# EJECTION_CIRCUIT.net
KiCad netlist of a schematic drawn in Altium Designer
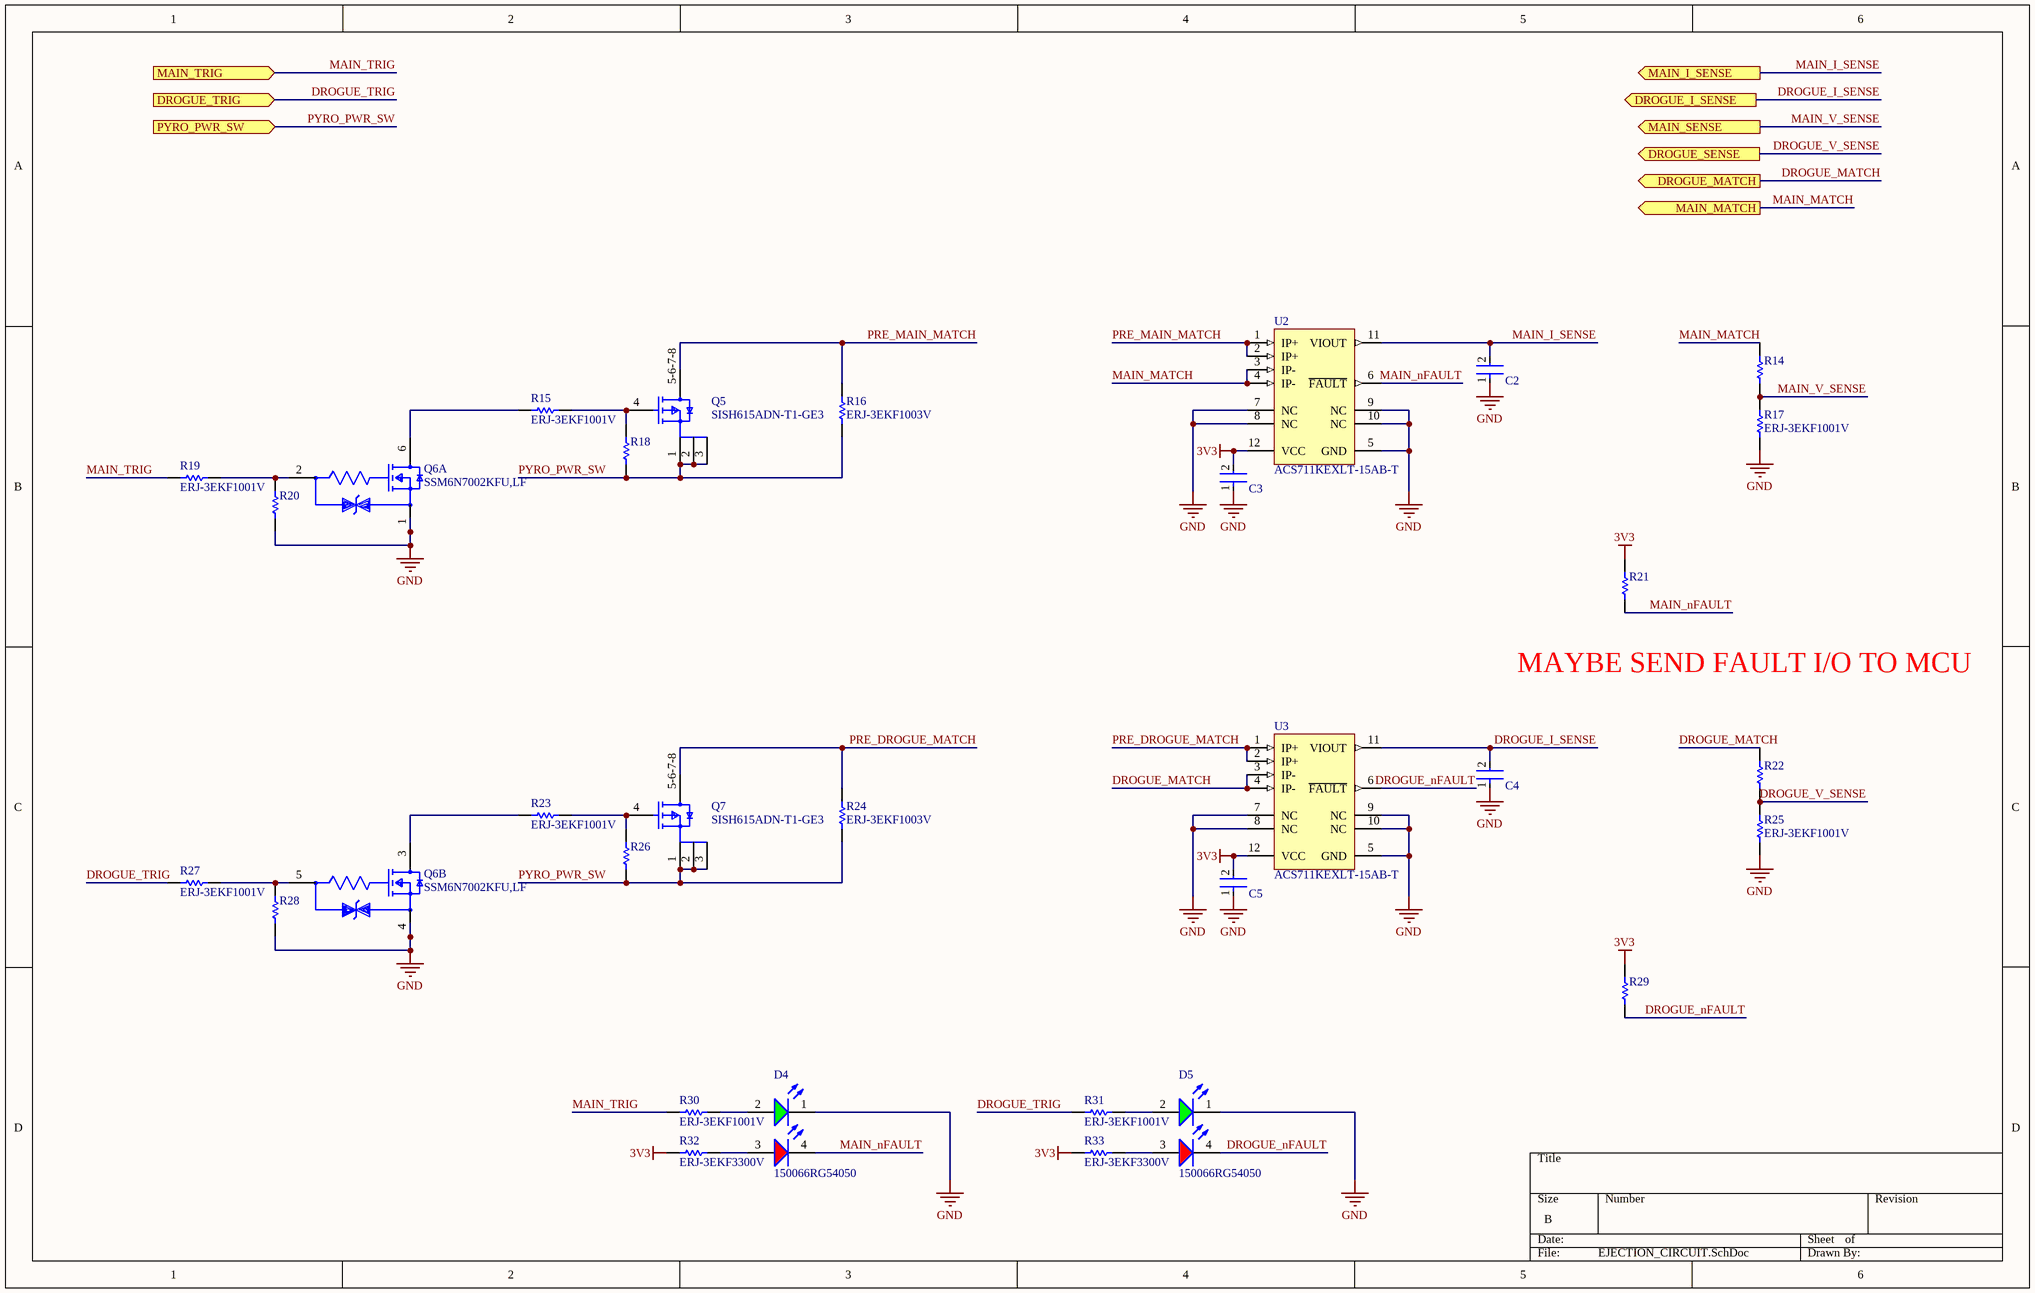
[diagram p0: EJECTION_CIRCUIT.SchDoc]

(export (version "E")
  (design (tool "Eeschema 10.0.6"))
  (components
    (comp (ref "C2")
      (value "C0402C104K8PACTU")
      (footprint "FP-C0402-BB-MFG")
      (description "CAP CER 0.1UF 10V X5R 0402")
      (fields (field (name "MANUFACTURER") "Kemet") (field (name "TOLERANCE") "0.1"))
      (libsource (lib "Altium Content Vault") (part "b4654b650e69147ec39a6b967a45e02"))
    )
    (comp (ref "C3")
      (value "C0402C104K8PACTU")
      (footprint "FP-C0402-BB-MFG")
      (description "CAP CER 0.1UF 10V X5R 0402")
      (fields (field (name "MANUFACTURER") "Kemet") (field (name "TOLERANCE") "0.1"))
      (libsource (lib "Altium Content Vault") (part "b4654b650e69147ec39a6b967a45e02"))
    )
    (comp (ref "C4")
      (value "C0402C104K8PACTU")
      (footprint "FP-C0402-BB-MFG")
      (description "CAP CER 0.1UF 10V X5R 0402")
      (fields (field (name "MANUFACTURER") "Kemet") (field (name "TOLERANCE") "0.1"))
      (libsource (lib "Altium Content Vault") (part "b4654b650e69147ec39a6b967a45e02"))
    )
    (comp (ref "C5")
      (value "C0402C104K8PACTU")
      (footprint "FP-C0402-BB-MFG")
      (description "CAP CER 0.1UF 10V X5R 0402")
      (fields (field (name "MANUFACTURER") "Kemet") (field (name "TOLERANCE") "0.1"))
      (libsource (lib "Altium Content Vault") (part "b4654b650e69147ec39a6b967a45e02"))
    )
    (comp (ref "D4")
      (value "150066RG54050")
      (footprint "WL-SBCD_0606")
      (description "Led, Red/Grn, 180Mcd/230Mcd, 624Nm/525Nm Rohs Compliant: Yes")
      (fields (field (name "SOURCE") "rgled.SchLib"))
      (libsource (lib "Space Concordia") (part "CMP-004-00034-2"))
    )
    (comp (ref "D5")
      (value "150066RG54050")
      (footprint "WL-SBCD_0606")
      (description "Led, Red/Grn, 180Mcd/230Mcd, 624Nm/525Nm Rohs Compliant: Yes")
      (fields (field (name "SOURCE") "rgled.SchLib"))
      (libsource (lib "Space Concordia") (part "CMP-004-00034-2"))
    )
    (comp (ref "Q5")
      (value "SISH615ADN-T1-GE3")
      (footprint "SISH615ADN-T1-GE3-Footprint-1")
      (description "Trans MOSFET P-CH 20V 22.1A 8-Pin PowerPAK 1212 EP T/R")
      (libsource (lib "Space Concordia") (part "CMP-013-00036-4"))
    )
    (comp (ref "Q6")
      (value "SSM6N7002KFU,LF")
      (footprint "FP-SSOP6-P-0_65A-MFG")
      (description "MOSFET 2N-CH 60V 0.3A")
      (libsource (lib "Altium Content Vault") (part "088aa6ac103fdeebe0d1c52ece6b7b9"))
    )
    (comp (ref "Q7")
      (value "SISH615ADN-T1-GE3")
      (footprint "SISH615ADN-T1-GE3-Footprint-1")
      (description "Trans MOSFET P-CH 20V 22.1A 8-Pin PowerPAK 1212 EP T/R")
      (libsource (lib "Space Concordia") (part "CMP-013-00036-4"))
    )
    (comp (ref "R14")
      (value "ERJ3EKF1002V")
      (footprint "RESC1609X55X30LL15T15")
      (description "Chip Resistor, 10 KOhm, +/- 1%, 0.1 W, -55 to 155 degC, 0603 (1608 Metric), RoHS, Tape and Reel")
      (fields (field (name "TOLERANCE") "1%") (field (name "MANUFACTURER") "Panasonic"))
      (libsource (lib "Altium Content Vault") (part "RES-2"))
    )
    (comp (ref "R15")
      (value "ERJ-3EKF1001V")
      (footprint "RESC1608X55X30LL15T15")
      (fields (field (name "MANUFACTURER") "Panasonic"))
      (libsource (lib "Altium Content Vault") (part "RES"))
    )
    (comp (ref "R16")
      (value "ERJ-3EKF1003V")
      (footprint "RESC1608X55X30ML15T15")
      (fields (field (name "MANUFACTURER") "Panasonic"))
      (libsource (lib "Altium Content Vault") (part "RES"))
    )
    (comp (ref "R17")
      (value "ERJ-3EKF1001V")
      (footprint "RESC1608X55X30LL15T15")
      (fields (field (name "MANUFACTURER") "Panasonic"))
      (libsource (lib "Altium Content Vault") (part "RES"))
    )
    (comp (ref "R18")
      (value "ERJ3EKF1002V")
      (footprint "RESC1609X55X30LL15T15")
      (description "Chip Resistor, 10 KOhm, +/- 1%, 0.1 W, -55 to 155 degC, 0603 (1608 Metric), RoHS, Tape and Reel")
      (fields (field (name "TOLERANCE") "1%") (field (name "MANUFACTURER") "Panasonic"))
      (libsource (lib "Altium Content Vault") (part "RES-2"))
    )
    (comp (ref "R19")
      (value "ERJ-3EKF1001V")
      (footprint "RESC1608X55X30LL15T15")
      (fields (field (name "MANUFACTURER") "Panasonic"))
      (libsource (lib "Altium Content Vault") (part "RES"))
    )
    (comp (ref "R20")
      (value "ERJ3EKF1002V")
      (footprint "RESC1609X55X30LL15T15")
      (description "Chip Resistor, 10 KOhm, +/- 1%, 0.1 W, -55 to 155 degC, 0603 (1608 Metric), RoHS, Tape and Reel")
      (fields (field (name "TOLERANCE") "1%") (field (name "MANUFACTURER") "Panasonic"))
      (libsource (lib "Altium Content Vault") (part "RES-2"))
    )
    (comp (ref "R21")
      (value "ERJ3EKF1002V")
      (footprint "RESC1609X55X30LL15T15")
      (description "Chip Resistor, 10 KOhm, +/- 1%, 0.1 W, -55 to 155 degC, 0603 (1608 Metric), RoHS, Tape and Reel")
      (fields (field (name "TOLERANCE") "1%") (field (name "MANUFACTURER") "Panasonic"))
      (libsource (lib "Altium Content Vault") (part "RES-2"))
    )
    (comp (ref "R22")
      (value "ERJ3EKF1002V")
      (footprint "RESC1609X55X30LL15T15")
      (description "Chip Resistor, 10 KOhm, +/- 1%, 0.1 W, -55 to 155 degC, 0603 (1608 Metric), RoHS, Tape and Reel")
      (fields (field (name "TOLERANCE") "1%") (field (name "MANUFACTURER") "Panasonic"))
      (libsource (lib "Altium Content Vault") (part "RES-2"))
    )
    (comp (ref "R23")
      (value "ERJ-3EKF1001V")
      (footprint "RESC1608X55X30LL15T15")
      (fields (field (name "MANUFACTURER") "Panasonic"))
      (libsource (lib "Altium Content Vault") (part "RES"))
    )
    (comp (ref "R24")
      (value "ERJ-3EKF1003V")
      (footprint "RESC1608X55X30ML15T15")
      (fields (field (name "MANUFACTURER") "Panasonic"))
      (libsource (lib "Altium Content Vault") (part "RES"))
    )
    (comp (ref "R25")
      (value "ERJ-3EKF1001V")
      (footprint "RESC1608X55X30LL15T15")
      (fields (field (name "MANUFACTURER") "Panasonic"))
      (libsource (lib "Altium Content Vault") (part "RES"))
    )
    (comp (ref "R26")
      (value "ERJ3EKF1002V")
      (footprint "RESC1609X55X30LL15T15")
      (description "Chip Resistor, 10 KOhm, +/- 1%, 0.1 W, -55 to 155 degC, 0603 (1608 Metric), RoHS, Tape and Reel")
      (fields (field (name "TOLERANCE") "1%") (field (name "MANUFACTURER") "Panasonic"))
      (libsource (lib "Altium Content Vault") (part "RES-2"))
    )
    (comp (ref "R27")
      (value "ERJ-3EKF1001V")
      (footprint "RESC1608X55X30LL15T15")
      (fields (field (name "MANUFACTURER") "Panasonic"))
      (libsource (lib "Altium Content Vault") (part "RES"))
    )
    (comp (ref "R28")
      (value "ERJ3EKF1002V")
      (footprint "RESC1609X55X30LL15T15")
      (description "Chip Resistor, 10 KOhm, +/- 1%, 0.1 W, -55 to 155 degC, 0603 (1608 Metric), RoHS, Tape and Reel")
      (fields (field (name "TOLERANCE") "1%") (field (name "MANUFACTURER") "Panasonic"))
      (libsource (lib "Altium Content Vault") (part "RES-2"))
    )
    (comp (ref "R29")
      (value "ERJ3EKF1002V")
      (footprint "RESC1609X55X30LL15T15")
      (description "Chip Resistor, 10 KOhm, +/- 1%, 0.1 W, -55 to 155 degC, 0603 (1608 Metric), RoHS, Tape and Reel")
      (fields (field (name "TOLERANCE") "1%") (field (name "MANUFACTURER") "Panasonic"))
      (libsource (lib "Altium Content Vault") (part "RES-2"))
    )
    (comp (ref "R30")
      (value "ERJ-3EKF1001V")
      (footprint "RESC1608X55X30LL15T15")
      (fields (field (name "MANUFACTURER") "Panasonic"))
      (libsource (lib "Altium Content Vault") (part "RES"))
    )
    (comp (ref "R31")
      (value "ERJ-3EKF1001V")
      (footprint "RESC1608X55X30LL15T15")
      (fields (field (name "MANUFACTURER") "Panasonic"))
      (libsource (lib "Altium Content Vault") (part "RES"))
    )
    (comp (ref "R32")
      (value "ERJ-3EKF3300V")
      (footprint "RESC1608X55X30LL15T15")
      (description "Chip Resistor, 330 Ohm, +/- 1%, 0.1 W, -55 to 155 degC, 0603 (1608 Metric), RoHS, Tape and Reel")
      (libsource (lib "Altium Content Vault") (part "RES-2"))
    )
    (comp (ref "R33")
      (value "ERJ-3EKF3300V")
      (footprint "RESC1608X55X30LL15T15")
      (description "Chip Resistor, 330 Ohm, +/- 1%, 0.1 W, -55 to 155 degC, 0603 (1608 Metric), RoHS, Tape and Reel")
      (libsource (lib "Altium Content Vault") (part "RES-2"))
    )
    (comp (ref "U2")
      (value "ACS711KEXLT-15AB-T")
      (footprint "ALEG-EX-12_V")
      (libsource (lib "Altium Content Vault") (part "ALEG-ACS711-QFN-12"))
    )
    (comp (ref "U3")
      (value "ACS711KEXLT-15AB-T")
      (footprint "ALEG-EX-12_V")
      (libsource (lib "Altium Content Vault") (part "ALEG-ACS711-QFN-12"))
    )
  )
  (nets
    (net (code "1") (name "/DROGUE_I_SENSE") (class "Default")
      (node (ref "C4") (pin "2") (pinfunction "2_2") (pintype "passive"))
      (node (ref "U3") (pin "11") (pinfunction "VIOUT_11") (pintype "output"))
    )
    (net (code "2") (name "/DROGUE_MATCH") (class "Default")
      (node (ref "R22") (pin "2") (pinfunction "2_2") (pintype "passive"))
      (node (ref "U3") (pin "3") (pinfunction "IP-_3") (pintype "input"))
      (node (ref "U3") (pin "4") (pinfunction "IP-_4") (pintype "input"))
    )
    (net (code "3") (name "/DROGUE_TRIG") (class "Default")
      (node (ref "R27") (pin "1") (pinfunction "1_1") (pintype "passive"))
      (node (ref "R31") (pin "1") (pinfunction "1_1") (pintype "passive"))
    )
    (net (code "4") (name "/DROGUE_V_SENSE") (class "Default")
      (node (ref "R22") (pin "1") (pinfunction "1_1") (pintype "passive"))
      (node (ref "R25") (pin "2") (pinfunction "2_2") (pintype "passive"))
    )
    (net (code "5") (name "/DROGUE_nFAULT") (class "Default")
      (node (ref "D5") (pin "4") (pinfunction "K_4") (pintype "passive"))
      (node (ref "R29") (pin "1") (pinfunction "1_1") (pintype "passive"))
      (node (ref "U3") (pin "6") (pinfunction "~{FAULT}_6") (pintype "output"))
    )
    (net (code "6") (name "/MAIN_I_SENSE") (class "Default")
      (node (ref "C2") (pin "2") (pinfunction "2_2") (pintype "passive"))
      (node (ref "U2") (pin "11") (pinfunction "VIOUT_11") (pintype "output"))
    )
    (net (code "7") (name "/MAIN_MATCH") (class "Default")
      (node (ref "R14") (pin "2") (pinfunction "2_2") (pintype "passive"))
      (node (ref "U2") (pin "3") (pinfunction "IP-_3") (pintype "input"))
      (node (ref "U2") (pin "4") (pinfunction "IP-_4") (pintype "input"))
    )
    (net (code "8") (name "/MAIN_TRIG") (class "Default")
      (node (ref "R19") (pin "1") (pinfunction "1_1") (pintype "passive"))
      (node (ref "R30") (pin "1") (pinfunction "1_1") (pintype "passive"))
    )
    (net (code "9") (name "/MAIN_V_SENSE") (class "Default")
      (node (ref "R14") (pin "1") (pinfunction "1_1") (pintype "passive"))
      (node (ref "R17") (pin "2") (pinfunction "2_2") (pintype "passive"))
    )
    (net (code "10") (name "/MAIN_nFAULT") (class "Default")
      (node (ref "D4") (pin "4") (pinfunction "K_4") (pintype "passive"))
      (node (ref "R21") (pin "1") (pinfunction "1_1") (pintype "passive"))
      (node (ref "U2") (pin "6") (pinfunction "~{FAULT}_6") (pintype "output"))
    )
    (net (code "11") (name "/PRE_DROGUE_MATCH") (class "Default")
      (node (ref "Q7") (pin "5-6-7-8") (pinfunction "D_5-6-7-8") (pintype "passive"))
      (node (ref "R24") (pin "2") (pinfunction "2_2") (pintype "passive"))
      (node (ref "U3") (pin "1") (pinfunction "IP+_1") (pintype "input"))
      (node (ref "U3") (pin "2") (pinfunction "IP+_2") (pintype "input"))
    )
    (net (code "12") (name "/PRE_MAIN_MATCH") (class "Default")
      (node (ref "Q5") (pin "5-6-7-8") (pinfunction "D_5-6-7-8") (pintype "passive"))
      (node (ref "R16") (pin "2") (pinfunction "2_2") (pintype "passive"))
      (node (ref "U2") (pin "1") (pinfunction "IP+_1") (pintype "input"))
      (node (ref "U2") (pin "2") (pinfunction "IP+_2") (pintype "input"))
    )
    (net (code "13") (name "/PYRO_PWR_SW") (class "Default")
      (node (ref "Q5") (pin "1") (pinfunction "S_1") (pintype "passive"))
      (node (ref "Q5") (pin "2") (pinfunction "S_2") (pintype "passive"))
      (node (ref "Q5") (pin "3") (pinfunction "S_3") (pintype "passive"))
      (node (ref "Q7") (pin "1") (pinfunction "S_1") (pintype "passive"))
      (node (ref "Q7") (pin "2") (pinfunction "S_2") (pintype "passive"))
      (node (ref "Q7") (pin "3") (pinfunction "S_3") (pintype "passive"))
      (node (ref "R16") (pin "1") (pinfunction "1_1") (pintype "passive"))
      (node (ref "R18") (pin "1") (pinfunction "1_1") (pintype "passive"))
      (node (ref "R24") (pin "1") (pinfunction "1_1") (pintype "passive"))
      (node (ref "R26") (pin "1") (pinfunction "1_1") (pintype "passive"))
    )
    (net (code "14") (name "3V3") (class "Default")
      (node (ref "C3") (pin "2") (pinfunction "2_2") (pintype "passive"))
      (node (ref "C5") (pin "2") (pinfunction "2_2") (pintype "passive"))
      (node (ref "R21") (pin "2") (pinfunction "2_2") (pintype "passive"))
      (node (ref "R29") (pin "2") (pinfunction "2_2") (pintype "passive"))
      (node (ref "R32") (pin "1") (pinfunction "1_1") (pintype "passive"))
      (node (ref "R33") (pin "1") (pinfunction "1_1") (pintype "passive"))
      (node (ref "U2") (pin "12") (pinfunction "VCC_12") (pintype "power_in"))
      (node (ref "U3") (pin "12") (pinfunction "VCC_12") (pintype "power_in"))
    )
    (net (code "15") (name "GND") (class "Default")
      (node (ref "C2") (pin "1") (pinfunction "1_1") (pintype "passive"))
      (node (ref "C3") (pin "1") (pinfunction "1_1") (pintype "passive"))
      (node (ref "C4") (pin "1") (pinfunction "1_1") (pintype "passive"))
      (node (ref "C5") (pin "1") (pinfunction "1_1") (pintype "passive"))
      (node (ref "D4") (pin "1") (pinfunction "K_1") (pintype "passive"))
      (node (ref "D5") (pin "1") (pinfunction "K_1") (pintype "passive"))
      (node (ref "Q6") (pin "1") (pinfunction "Source1_1") (pintype "passive"))
      (node (ref "Q6") (pin "4") (pinfunction "Source2_4") (pintype "passive"))
      (node (ref "R17") (pin "1") (pinfunction "1_1") (pintype "passive"))
      (node (ref "R20") (pin "1") (pinfunction "1_1") (pintype "passive"))
      (node (ref "R25") (pin "1") (pinfunction "1_1") (pintype "passive"))
      (node (ref "R28") (pin "1") (pinfunction "1_1") (pintype "passive"))
      (node (ref "U2") (pin "10") (pinfunction "NC_10") (pintype "passive"))
      (node (ref "U2") (pin "5") (pinfunction "GND_5") (pintype "power_in"))
      (node (ref "U2") (pin "7") (pinfunction "NC_7") (pintype "passive"))
      (node (ref "U2") (pin "8") (pinfunction "NC_8") (pintype "passive"))
      (node (ref "U2") (pin "9") (pinfunction "NC_9") (pintype "passive"))
      (node (ref "U3") (pin "10") (pinfunction "NC_10") (pintype "passive"))
      (node (ref "U3") (pin "5") (pinfunction "GND_5") (pintype "power_in"))
      (node (ref "U3") (pin "7") (pinfunction "NC_7") (pintype "passive"))
      (node (ref "U3") (pin "8") (pinfunction "NC_8") (pintype "passive"))
      (node (ref "U3") (pin "9") (pinfunction "NC_9") (pintype "passive"))
    )
    (net (code "16") (name "Net-(D4-A-Pad2)") (class "Default")
      (node (ref "D4") (pin "2") (pinfunction "A_2") (pintype "passive"))
      (node (ref "R30") (pin "2") (pinfunction "2_2") (pintype "passive"))
    )
    (net (code "17") (name "Net-(D4-A-Pad3)") (class "Default")
      (node (ref "D4") (pin "3") (pinfunction "A_3") (pintype "passive"))
      (node (ref "R32") (pin "2") (pinfunction "2_2") (pintype "passive"))
    )
    (net (code "18") (name "Net-(D5-A-Pad2)") (class "Default")
      (node (ref "D5") (pin "2") (pinfunction "A_2") (pintype "passive"))
      (node (ref "R31") (pin "2") (pinfunction "2_2") (pintype "passive"))
    )
    (net (code "19") (name "Net-(D5-A-Pad3)") (class "Default")
      (node (ref "D5") (pin "3") (pinfunction "A_3") (pintype "passive"))
      (node (ref "R33") (pin "2") (pinfunction "2_2") (pintype "passive"))
    )
    (net (code "20") (name "Net-(Q5-G)") (class "Default")
      (node (ref "Q5") (pin "4") (pinfunction "G_4") (pintype "passive"))
      (node (ref "R15") (pin "2") (pinfunction "2_2") (pintype "passive"))
      (node (ref "R18") (pin "2") (pinfunction "2_2") (pintype "passive"))
    )
    (net (code "21") (name "Net-(Q6A-Drain1)") (class "Default")
      (node (ref "Q6") (pin "6") (pinfunction "Drain1_6") (pintype "passive"))
      (node (ref "R15") (pin "1") (pinfunction "1_1") (pintype "passive"))
    )
    (net (code "22") (name "Net-(Q6A-Gate1)") (class "Default")
      (node (ref "Q6") (pin "2") (pinfunction "Gate1_2") (pintype "passive"))
      (node (ref "R19") (pin "2") (pinfunction "2_2") (pintype "passive"))
      (node (ref "R20") (pin "2") (pinfunction "2_2") (pintype "passive"))
    )
    (net (code "23") (name "Net-(Q6B-Drain2)") (class "Default")
      (node (ref "Q6") (pin "3") (pinfunction "Drain2_3") (pintype "passive"))
      (node (ref "R23") (pin "1") (pinfunction "1_1") (pintype "passive"))
    )
    (net (code "24") (name "Net-(Q6B-Gate2)") (class "Default")
      (node (ref "Q6") (pin "5") (pinfunction "Gate2_5") (pintype "passive"))
      (node (ref "R27") (pin "2") (pinfunction "2_2") (pintype "passive"))
      (node (ref "R28") (pin "2") (pinfunction "2_2") (pintype "passive"))
    )
    (net (code "25") (name "Net-(Q7-G)") (class "Default")
      (node (ref "Q7") (pin "4") (pinfunction "G_4") (pintype "passive"))
      (node (ref "R23") (pin "2") (pinfunction "2_2") (pintype "passive"))
      (node (ref "R26") (pin "2") (pinfunction "2_2") (pintype "passive"))
    )
  )
)
